# Wiring_Harness_Spec.net
KiCad netlist of a schematic drawn in Altium Designer
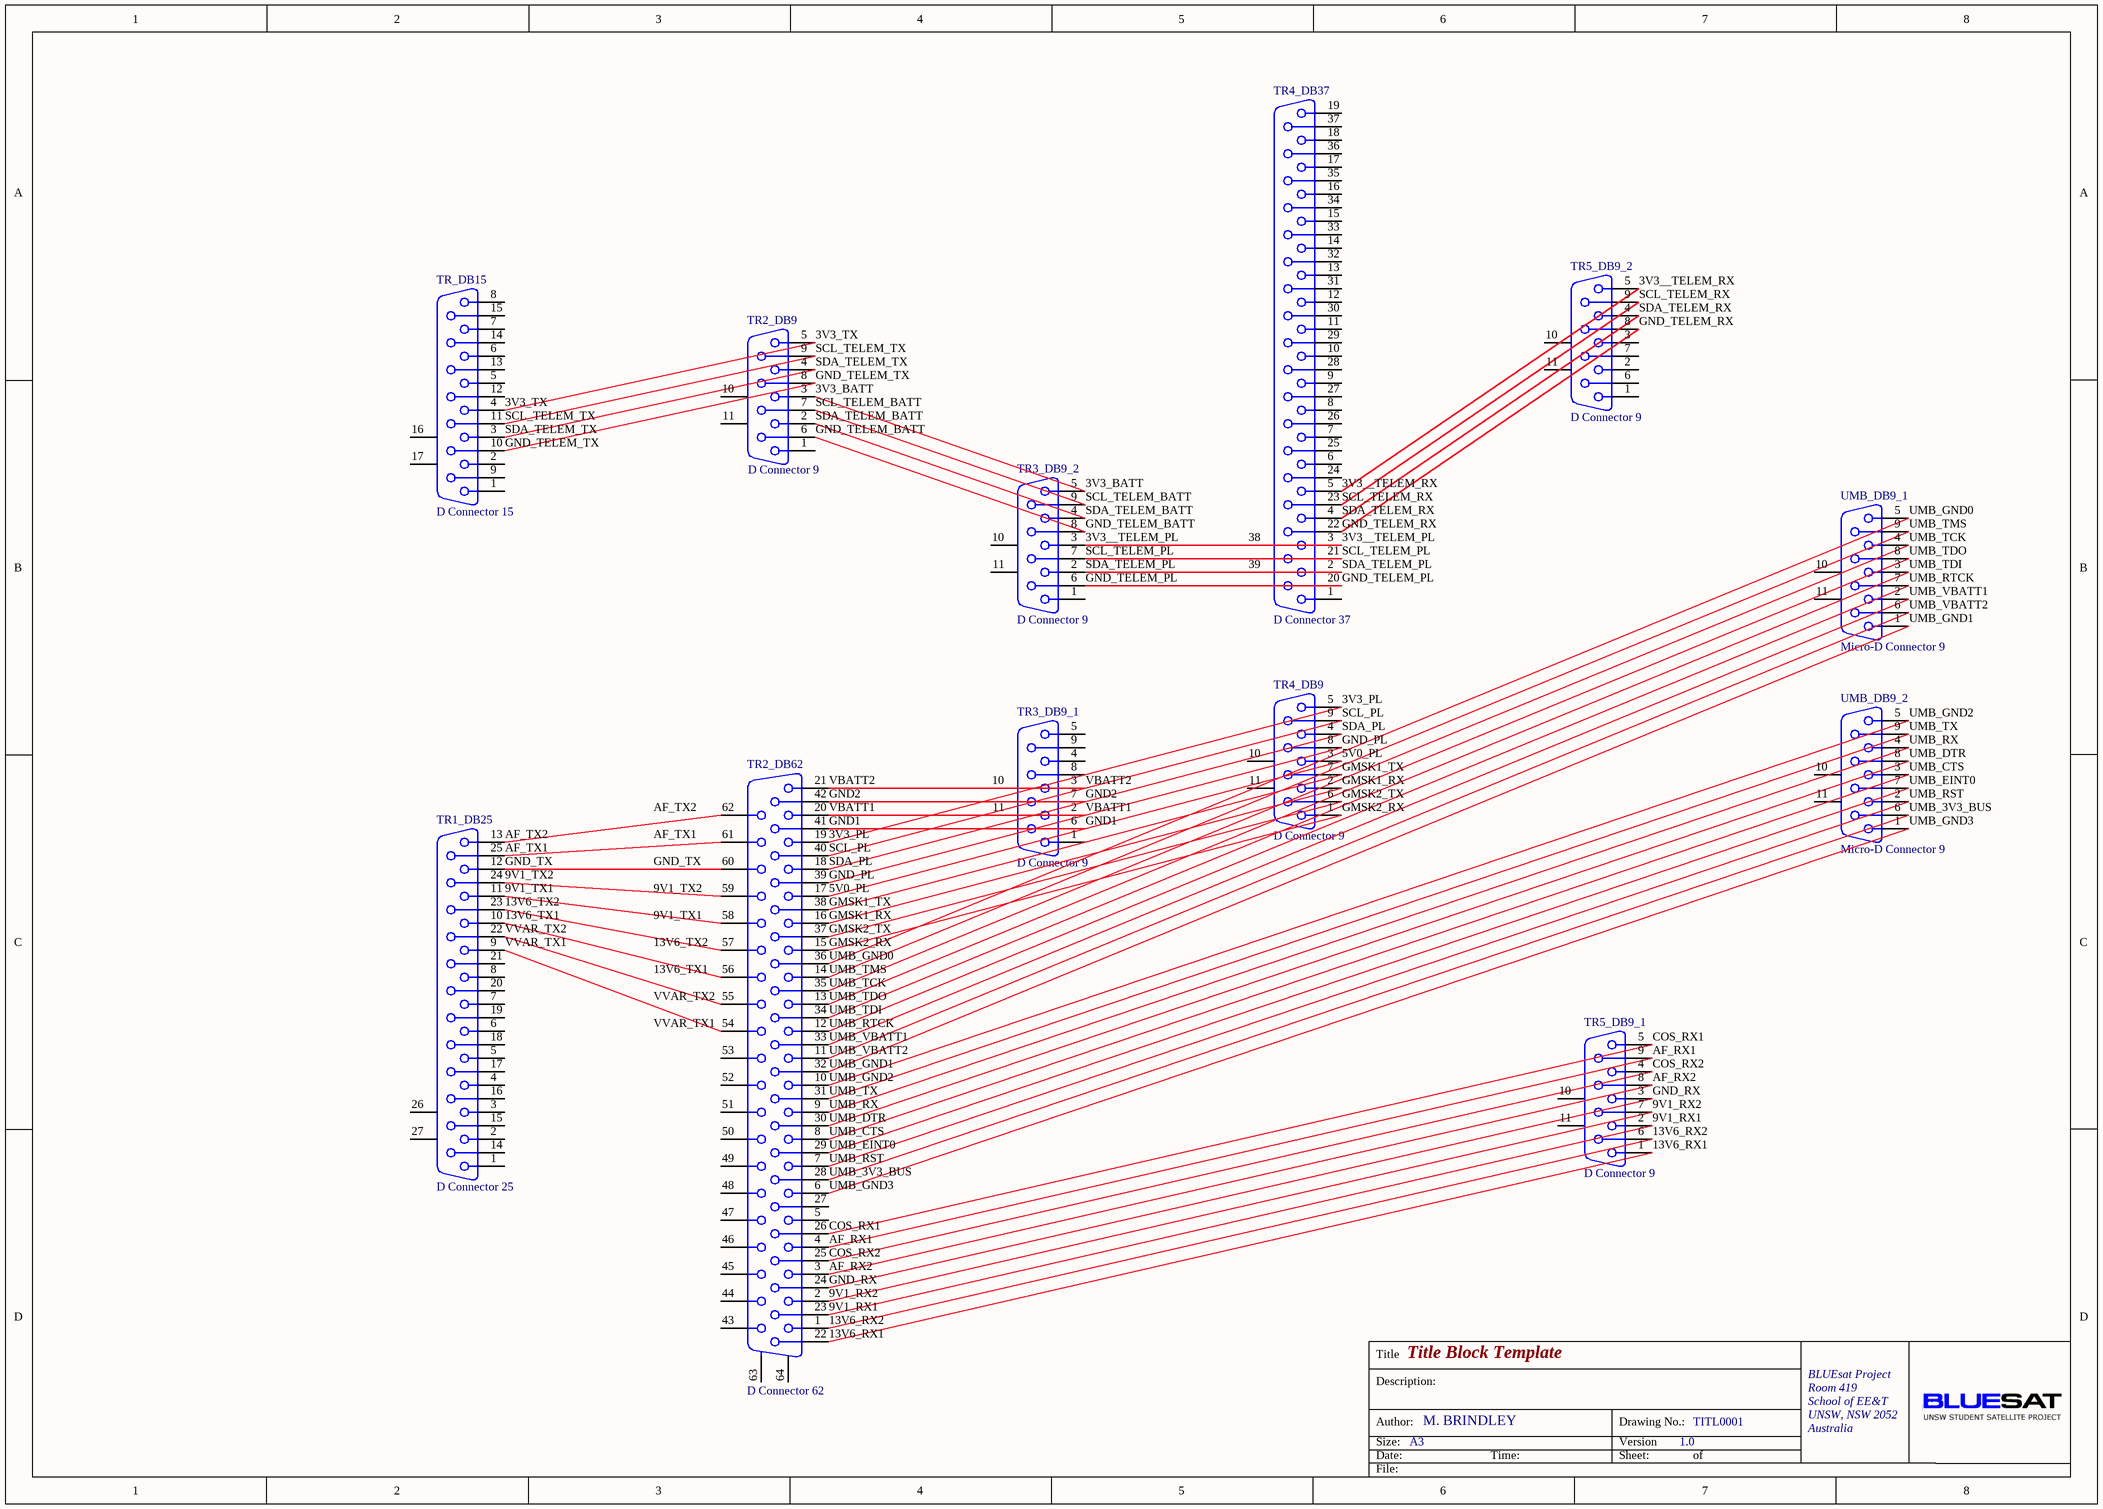
[diagram p0: Wiring Harness Spec.SchDoc]

(export (version "E")
  (design (tool "Eeschema 10.0.6"))
  (components
    (comp (ref "TR1_DB25")
      (value "D Connector 25")
      (footprint "DSUB1.385-2H25A")
      (description "Receptacle Assembly, 25 Position, Right Angle")
      (fields (field (name "PUBLISHER") "Altium Limited"))
      (libsource (lib "Miscellaneous Connectors") (part "D Connector 25"))
    )
    (comp (ref "TR2_DB9")
      (value "D Connector 9")
      (footprint "DSUB1.385-2H9")
      (description "Receptacle Assembly, 9 Position, Right Angle")
      (fields (field (name "PUBLISHER") "Altium Limited"))
      (libsource (lib "Miscellaneous Connectors") (part "D Connector 9"))
    )
    (comp (ref "TR2_DB62")
      (value "D Connector 62")
      (footprint "HD-22 62 POS")
      (libsource (lib "Tray2Mobo") (part "Connector 62"))
    )
    (comp (ref "TR3_DB9_1")
      (value "D Connector 9")
      (footprint "DSUB1.385-2H9")
      (description "Receptacle Assembly, 9 Position, Right Angle")
      (fields (field (name "PUBLISHER") "Altium Limited"))
      (libsource (lib "Miscellaneous Connectors") (part "D Connector 9"))
    )
    (comp (ref "TR3_DB9_2")
      (value "D Connector 9")
      (footprint "DSUB1.385-2H9")
      (description "Receptacle Assembly, 9 Position, Right Angle")
      (fields (field (name "PUBLISHER") "Altium Limited"))
      (libsource (lib "Miscellaneous Connectors") (part "D Connector 9"))
    )
    (comp (ref "TR4_DB9")
      (value "D Connector 9")
      (footprint "DSUB1.385-2H9")
      (description "Receptacle Assembly, 9 Position, Right Angle")
      (fields (field (name "PUBLISHER") "Altium Limited"))
      (libsource (lib "Miscellaneous Connectors") (part "D Connector 9"))
    )
    (comp (ref "TR4_DB37")
      (value "D Connector 37")
      (description "Receptacle Assembly, 37 Position, Right Angle")
      (fields (field (name "PUBLISHER") "Altium Limited"))
      (libsource (lib "Miscellaneous Connectors") (part "D Connector 37"))
    )
    (comp (ref "TR5_DB9_1")
      (value "D Connector 9")
      (footprint "DSUB1.385-2H9")
      (description "Receptacle Assembly, 9 Position, Right Angle")
      (fields (field (name "PUBLISHER") "Altium Limited"))
      (libsource (lib "Miscellaneous Connectors") (part "D Connector 9"))
    )
    (comp (ref "TR5_DB9_2")
      (value "D Connector 9")
      (footprint "DSUB1.385-2H9")
      (description "Receptacle Assembly, 9 Position, Right Angle")
      (fields (field (name "PUBLISHER") "Altium Limited"))
      (libsource (lib "Miscellaneous Connectors") (part "D Connector 9"))
    )
    (comp (ref "TR_DB15")
      (value "D Connector 15")
      (footprint "DSUB1.385-2H15")
      (description "Receptacle Assembly, 15 Position, Right Angle")
      (fields (field (name "PUBLISHER") "Altium Limited"))
      (libsource (lib "Miscellaneous Connectors") (part "D Connector 15"))
    )
    (comp (ref "UMB_DB9_1")
      (value "Micro-D Connector 9")
      (footprint "DSUB1.385-2H9")
      (description "Receptacle Assembly, 9 Position, Right Angle")
      (fields (field (name "PUBLISHER") "Altium Limited"))
      (libsource (lib "Miscellaneous Connectors") (part "D Connector 9"))
    )
    (comp (ref "UMB_DB9_2")
      (value "Micro-D Connector 9")
      (footprint "DSUB1.385-2H9")
      (description "Receptacle Assembly, 9 Position, Right Angle")
      (fields (field (name "PUBLISHER") "Altium Limited"))
      (libsource (lib "Miscellaneous Connectors") (part "D Connector 9"))
    )
  )
  (nets
    (net (code "1") (name "/3V3_BATT") (class "Default")
      (node (ref "TR2_DB9") (pin "3") (pinfunction "3_3") (pintype "passive"))
      (node (ref "TR3_DB9_2") (pin "5") (pinfunction "5_5") (pintype "passive"))
    )
    (net (code "2") (name "/3V3_PL") (class "Default")
      (node (ref "TR2_DB62") (pin "19") (pinfunction "19_19") (pintype "passive"))
      (node (ref "TR4_DB9") (pin "5") (pinfunction "5_5") (pintype "passive"))
    )
    (net (code "3") (name "/3V3_TX") (class "Default")
      (node (ref "TR2_DB9") (pin "5") (pinfunction "5_5") (pintype "passive"))
      (node (ref "TR_DB15") (pin "4") (pinfunction "4_4") (pintype "passive"))
    )
    (net (code "4") (name "/3V3__TELEM_PL") (class "Default")
      (node (ref "TR3_DB9_2") (pin "3") (pinfunction "3_3") (pintype "passive"))
      (node (ref "TR4_DB37") (pin "3") (pinfunction "3_3") (pintype "passive"))
    )
    (net (code "5") (name "/3V3__TELEM_RX") (class "Default")
      (node (ref "TR4_DB37") (pin "5") (pinfunction "5_5") (pintype "passive"))
      (node (ref "TR5_DB9_2") (pin "5") (pinfunction "5_5") (pintype "passive"))
    )
    (net (code "6") (name "/5V0_PL") (class "Default")
      (node (ref "TR2_DB62") (pin "17") (pinfunction "17_17") (pintype "passive"))
      (node (ref "TR4_DB9") (pin "3") (pinfunction "3_3") (pintype "passive"))
    )
    (net (code "7") (name "/9V1_RX1") (class "Default")
      (node (ref "TR2_DB62") (pin "23") (pinfunction "23_23") (pintype "passive"))
      (node (ref "TR5_DB9_1") (pin "2") (pinfunction "2_2") (pintype "passive"))
    )
    (net (code "8") (name "/9V1_RX2") (class "Default")
      (node (ref "TR2_DB62") (pin "2") (pinfunction "2_2") (pintype "passive"))
      (node (ref "TR5_DB9_1") (pin "7") (pinfunction "7_7") (pintype "passive"))
    )
    (net (code "9") (name "/9V1_TX1") (class "Default")
      (node (ref "TR1_DB25") (pin "11") (pinfunction "11_11") (pintype "passive"))
    )
    (net (code "10") (name "/9V1_TX2") (class "Default")
      (node (ref "TR1_DB25") (pin "24") (pinfunction "24_24") (pintype "passive"))
    )
    (net (code "11") (name "/13V6_RX1") (class "Default")
      (node (ref "TR2_DB62") (pin "22") (pinfunction "22_22") (pintype "passive"))
      (node (ref "TR5_DB9_1") (pin "1") (pinfunction "1_1") (pintype "passive"))
    )
    (net (code "12") (name "/13V6_RX2") (class "Default")
      (node (ref "TR2_DB62") (pin "1") (pinfunction "1_1") (pintype "passive"))
      (node (ref "TR5_DB9_1") (pin "6") (pinfunction "6_6") (pintype "passive"))
    )
    (net (code "13") (name "/13V6_TX1") (class "Default")
      (node (ref "TR1_DB25") (pin "10") (pinfunction "10_10") (pintype "passive"))
    )
    (net (code "14") (name "/13V6_TX2") (class "Default")
      (node (ref "TR1_DB25") (pin "23") (pinfunction "23_23") (pintype "passive"))
    )
    (net (code "15") (name "/AF_RX1") (class "Default")
      (node (ref "TR2_DB62") (pin "4") (pinfunction "4_4") (pintype "passive"))
      (node (ref "TR5_DB9_1") (pin "9") (pinfunction "9_9") (pintype "passive"))
    )
    (net (code "16") (name "/AF_RX2") (class "Default")
      (node (ref "TR2_DB62") (pin "3") (pinfunction "3_3") (pintype "passive"))
      (node (ref "TR5_DB9_1") (pin "8") (pinfunction "8_8") (pintype "passive"))
    )
    (net (code "17") (name "/AF_TX1") (class "Default")
      (node (ref "TR1_DB25") (pin "25") (pinfunction "25_25") (pintype "passive"))
    )
    (net (code "18") (name "/AF_TX2") (class "Default")
      (node (ref "TR1_DB25") (pin "13") (pinfunction "13_13") (pintype "passive"))
    )
    (net (code "19") (name "/COS_RX1") (class "Default")
      (node (ref "TR2_DB62") (pin "26") (pinfunction "26_26") (pintype "passive"))
      (node (ref "TR5_DB9_1") (pin "5") (pinfunction "5_5") (pintype "passive"))
    )
    (net (code "20") (name "/COS_RX2") (class "Default")
      (node (ref "TR2_DB62") (pin "25") (pinfunction "25_25") (pintype "passive"))
      (node (ref "TR5_DB9_1") (pin "4") (pinfunction "4_4") (pintype "passive"))
    )
    (net (code "21") (name "/GMSK1_RX") (class "Default")
      (node (ref "TR2_DB62") (pin "16") (pinfunction "16_16") (pintype "passive"))
      (node (ref "TR4_DB9") (pin "2") (pinfunction "2_2") (pintype "passive"))
    )
    (net (code "22") (name "/GMSK1_TX") (class "Default")
      (node (ref "TR2_DB62") (pin "38") (pinfunction "38_38") (pintype "passive"))
      (node (ref "TR4_DB9") (pin "7") (pinfunction "7_7") (pintype "passive"))
    )
    (net (code "23") (name "/GMSK2_RX") (class "Default")
      (node (ref "TR2_DB62") (pin "15") (pinfunction "15_15") (pintype "passive"))
      (node (ref "TR4_DB9") (pin "1") (pinfunction "1_1") (pintype "passive"))
    )
    (net (code "24") (name "/GMSK2_TX") (class "Default")
      (node (ref "TR2_DB62") (pin "37") (pinfunction "37_37") (pintype "passive"))
      (node (ref "TR4_DB9") (pin "6") (pinfunction "6_6") (pintype "passive"))
    )
    (net (code "25") (name "/GND1") (class "Default")
      (node (ref "TR2_DB62") (pin "41") (pinfunction "41_41") (pintype "passive"))
      (node (ref "TR3_DB9_1") (pin "6") (pinfunction "6_6") (pintype "passive"))
    )
    (net (code "26") (name "/GND2") (class "Default")
      (node (ref "TR2_DB62") (pin "42") (pinfunction "42_42") (pintype "passive"))
      (node (ref "TR3_DB9_1") (pin "7") (pinfunction "7_7") (pintype "passive"))
    )
    (net (code "27") (name "/GND_PL") (class "Default")
      (node (ref "TR2_DB62") (pin "39") (pinfunction "39_39") (pintype "passive"))
      (node (ref "TR4_DB9") (pin "8") (pinfunction "8_8") (pintype "passive"))
    )
    (net (code "28") (name "/GND_RX") (class "Default")
      (node (ref "TR2_DB62") (pin "24") (pinfunction "24_24") (pintype "passive"))
      (node (ref "TR5_DB9_1") (pin "3") (pinfunction "3_3") (pintype "passive"))
    )
    (net (code "29") (name "/GND_TELEM_BATT") (class "Default")
      (node (ref "TR2_DB9") (pin "6") (pinfunction "6_6") (pintype "passive"))
      (node (ref "TR3_DB9_2") (pin "8") (pinfunction "8_8") (pintype "passive"))
    )
    (net (code "30") (name "/GND_TELEM_PL") (class "Default")
      (node (ref "TR3_DB9_2") (pin "6") (pinfunction "6_6") (pintype "passive"))
      (node (ref "TR4_DB37") (pin "20") (pinfunction "20_20") (pintype "passive"))
    )
    (net (code "31") (name "/GND_TELEM_RX") (class "Default")
      (node (ref "TR4_DB37") (pin "22") (pinfunction "22_22") (pintype "passive"))
      (node (ref "TR5_DB9_2") (pin "8") (pinfunction "8_8") (pintype "passive"))
    )
    (net (code "32") (name "/GND_TELEM_TX") (class "Default")
      (node (ref "TR2_DB9") (pin "8") (pinfunction "8_8") (pintype "passive"))
      (node (ref "TR_DB15") (pin "10") (pinfunction "10_10") (pintype "passive"))
    )
    (net (code "33") (name "/GND_TX") (class "Default")
      (node (ref "TR1_DB25") (pin "12") (pinfunction "12_12") (pintype "passive"))
    )
    (net (code "34") (name "/SCL_PL") (class "Default")
      (node (ref "TR2_DB62") (pin "40") (pinfunction "40_40") (pintype "passive"))
      (node (ref "TR4_DB9") (pin "9") (pinfunction "9_9") (pintype "passive"))
    )
    (net (code "35") (name "/SCL_TELEM_BATT") (class "Default")
      (node (ref "TR2_DB9") (pin "7") (pinfunction "7_7") (pintype "passive"))
      (node (ref "TR3_DB9_2") (pin "9") (pinfunction "9_9") (pintype "passive"))
    )
    (net (code "36") (name "/SCL_TELEM_PL") (class "Default")
      (node (ref "TR3_DB9_2") (pin "7") (pinfunction "7_7") (pintype "passive"))
      (node (ref "TR4_DB37") (pin "21") (pinfunction "21_21") (pintype "passive"))
    )
    (net (code "37") (name "/SCL_TELEM_RX") (class "Default")
      (node (ref "TR4_DB37") (pin "23") (pinfunction "23_23") (pintype "passive"))
      (node (ref "TR5_DB9_2") (pin "9") (pinfunction "9_9") (pintype "passive"))
    )
    (net (code "38") (name "/SCL_TELEM_TX") (class "Default")
      (node (ref "TR2_DB9") (pin "9") (pinfunction "9_9") (pintype "passive"))
      (node (ref "TR_DB15") (pin "11") (pinfunction "11_11") (pintype "passive"))
    )
    (net (code "39") (name "/SDA_PL") (class "Default")
      (node (ref "TR2_DB62") (pin "18") (pinfunction "18_18") (pintype "passive"))
      (node (ref "TR4_DB9") (pin "4") (pinfunction "4_4") (pintype "passive"))
    )
    (net (code "40") (name "/SDA_TELEM_BATT") (class "Default")
      (node (ref "TR2_DB9") (pin "2") (pinfunction "2_2") (pintype "passive"))
      (node (ref "TR3_DB9_2") (pin "4") (pinfunction "4_4") (pintype "passive"))
    )
    (net (code "41") (name "/SDA_TELEM_PL") (class "Default")
      (node (ref "TR3_DB9_2") (pin "2") (pinfunction "2_2") (pintype "passive"))
      (node (ref "TR4_DB37") (pin "2") (pinfunction "2_2") (pintype "passive"))
    )
    (net (code "42") (name "/SDA_TELEM_RX") (class "Default")
      (node (ref "TR4_DB37") (pin "4") (pinfunction "4_4") (pintype "passive"))
      (node (ref "TR5_DB9_2") (pin "4") (pinfunction "4_4") (pintype "passive"))
    )
    (net (code "43") (name "/SDA_TELEM_TX") (class "Default")
      (node (ref "TR2_DB9") (pin "4") (pinfunction "4_4") (pintype "passive"))
      (node (ref "TR_DB15") (pin "3") (pinfunction "3_3") (pintype "passive"))
    )
    (net (code "44") (name "/UMB_3V3_BUS") (class "Default")
      (node (ref "TR2_DB62") (pin "28") (pinfunction "28_28") (pintype "passive"))
      (node (ref "UMB_DB9_2") (pin "6") (pinfunction "6_6") (pintype "passive"))
    )
    (net (code "45") (name "/UMB_CTS") (class "Default")
      (node (ref "TR2_DB62") (pin "8") (pinfunction "8_8") (pintype "passive"))
      (node (ref "UMB_DB9_2") (pin "3") (pinfunction "3_3") (pintype "passive"))
    )
    (net (code "46") (name "/UMB_DTR") (class "Default")
      (node (ref "TR2_DB62") (pin "30") (pinfunction "30_30") (pintype "passive"))
      (node (ref "UMB_DB9_2") (pin "8") (pinfunction "8_8") (pintype "passive"))
    )
    (net (code "47") (name "/UMB_EINT0") (class "Default")
      (node (ref "TR2_DB62") (pin "29") (pinfunction "29_29") (pintype "passive"))
      (node (ref "UMB_DB9_2") (pin "7") (pinfunction "7_7") (pintype "passive"))
    )
    (net (code "48") (name "/UMB_GND0") (class "Default")
      (node (ref "TR2_DB62") (pin "36") (pinfunction "36_36") (pintype "passive"))
      (node (ref "UMB_DB9_1") (pin "5") (pinfunction "5_5") (pintype "passive"))
    )
    (net (code "49") (name "/UMB_GND1") (class "Default")
      (node (ref "TR2_DB62") (pin "32") (pinfunction "32_32") (pintype "passive"))
      (node (ref "UMB_DB9_1") (pin "1") (pinfunction "1_1") (pintype "passive"))
    )
    (net (code "50") (name "/UMB_GND2") (class "Default")
      (node (ref "TR2_DB62") (pin "10") (pinfunction "10_10") (pintype "passive"))
      (node (ref "UMB_DB9_2") (pin "5") (pinfunction "5_5") (pintype "passive"))
    )
    (net (code "51") (name "/UMB_GND3") (class "Default")
      (node (ref "TR2_DB62") (pin "6") (pinfunction "6_6") (pintype "passive"))
      (node (ref "UMB_DB9_2") (pin "1") (pinfunction "1_1") (pintype "passive"))
    )
    (net (code "52") (name "/UMB_RST") (class "Default")
      (node (ref "TR2_DB62") (pin "7") (pinfunction "7_7") (pintype "passive"))
      (node (ref "UMB_DB9_2") (pin "2") (pinfunction "2_2") (pintype "passive"))
    )
    (net (code "53") (name "/UMB_RTCK") (class "Default")
      (node (ref "TR2_DB62") (pin "12") (pinfunction "12_12") (pintype "passive"))
      (node (ref "UMB_DB9_1") (pin "7") (pinfunction "7_7") (pintype "passive"))
    )
    (net (code "54") (name "/UMB_RX") (class "Default")
      (node (ref "TR2_DB62") (pin "9") (pinfunction "9_9") (pintype "passive"))
      (node (ref "UMB_DB9_2") (pin "4") (pinfunction "4_4") (pintype "passive"))
    )
    (net (code "55") (name "/UMB_TCK") (class "Default")
      (node (ref "TR2_DB62") (pin "35") (pinfunction "35_35") (pintype "passive"))
      (node (ref "UMB_DB9_1") (pin "4") (pinfunction "4_4") (pintype "passive"))
    )
    (net (code "56") (name "/UMB_TDI") (class "Default")
      (node (ref "TR2_DB62") (pin "34") (pinfunction "34_34") (pintype "passive"))
      (node (ref "UMB_DB9_1") (pin "3") (pinfunction "3_3") (pintype "passive"))
    )
    (net (code "57") (name "/UMB_TDO") (class "Default")
      (node (ref "TR2_DB62") (pin "13") (pinfunction "13_13") (pintype "passive"))
      (node (ref "UMB_DB9_1") (pin "8") (pinfunction "8_8") (pintype "passive"))
    )
    (net (code "58") (name "/UMB_TMS") (class "Default")
      (node (ref "TR2_DB62") (pin "14") (pinfunction "14_14") (pintype "passive"))
      (node (ref "UMB_DB9_1") (pin "9") (pinfunction "9_9") (pintype "passive"))
    )
    (net (code "59") (name "/UMB_TX") (class "Default")
      (node (ref "TR2_DB62") (pin "31") (pinfunction "31_31") (pintype "passive"))
      (node (ref "UMB_DB9_2") (pin "9") (pinfunction "9_9") (pintype "passive"))
    )
    (net (code "60") (name "/UMB_VBATT1") (class "Default")
      (node (ref "TR2_DB62") (pin "33") (pinfunction "33_33") (pintype "passive"))
      (node (ref "UMB_DB9_1") (pin "2") (pinfunction "2_2") (pintype "passive"))
    )
    (net (code "61") (name "/UMB_VBATT2") (class "Default")
      (node (ref "TR2_DB62") (pin "11") (pinfunction "11_11") (pintype "passive"))
      (node (ref "UMB_DB9_1") (pin "6") (pinfunction "6_6") (pintype "passive"))
    )
    (net (code "62") (name "/VBATT1") (class "Default")
      (node (ref "TR2_DB62") (pin "20") (pinfunction "20_20") (pintype "passive"))
      (node (ref "TR3_DB9_1") (pin "2") (pinfunction "2_2") (pintype "passive"))
    )
    (net (code "63") (name "/VBATT2") (class "Default")
      (node (ref "TR2_DB62") (pin "21") (pinfunction "21_21") (pintype "passive"))
      (node (ref "TR3_DB9_1") (pin "3") (pinfunction "3_3") (pintype "passive"))
    )
    (net (code "64") (name "/VVAR_TX1") (class "Default")
      (node (ref "TR1_DB25") (pin "9") (pinfunction "9_9") (pintype "passive"))
    )
    (net (code "65") (name "/VVAR_TX2") (class "Default")
      (node (ref "TR1_DB25") (pin "22") (pinfunction "22_22") (pintype "passive"))
    )
    (net (code "66") (name "unconnected-(TR1_DB25-MH1-Pad26)") (class "Default")
      (node (ref "TR1_DB25") (pin "26") (pinfunction "MH1_26") (pintype "passive"))
    )
    (net (code "67") (name "unconnected-(TR1_DB25-MH2-Pad27)") (class "Default")
      (node (ref "TR1_DB25") (pin "27") (pinfunction "MH2_27") (pintype "passive"))
    )
    (net (code "68") (name "unconnected-(TR1_DB25-Pad1)") (class "Default")
      (node (ref "TR1_DB25") (pin "1") (pinfunction "1_1") (pintype "passive"))
    )
    (net (code "69") (name "unconnected-(TR1_DB25-Pad2)") (class "Default")
      (node (ref "TR1_DB25") (pin "2") (pinfunction "2_2") (pintype "passive"))
    )
    (net (code "70") (name "unconnected-(TR1_DB25-Pad3)") (class "Default")
      (node (ref "TR1_DB25") (pin "3") (pinfunction "3_3") (pintype "passive"))
    )
    (net (code "71") (name "unconnected-(TR1_DB25-Pad4)") (class "Default")
      (node (ref "TR1_DB25") (pin "4") (pinfunction "4_4") (pintype "passive"))
    )
    (net (code "72") (name "unconnected-(TR1_DB25-Pad5)") (class "Default")
      (node (ref "TR1_DB25") (pin "5") (pinfunction "5_5") (pintype "passive"))
    )
    (net (code "73") (name "unconnected-(TR1_DB25-Pad6)") (class "Default")
      (node (ref "TR1_DB25") (pin "6") (pinfunction "6_6") (pintype "passive"))
    )
    (net (code "74") (name "unconnected-(TR1_DB25-Pad7)") (class "Default")
      (node (ref "TR1_DB25") (pin "7") (pinfunction "7_7") (pintype "passive"))
    )
    (net (code "75") (name "unconnected-(TR1_DB25-Pad8)") (class "Default")
      (node (ref "TR1_DB25") (pin "8") (pinfunction "8_8") (pintype "passive"))
    )
    (net (code "76") (name "unconnected-(TR1_DB25-Pad14)") (class "Default")
      (node (ref "TR1_DB25") (pin "14") (pinfunction "14_14") (pintype "passive"))
    )
    (net (code "77") (name "unconnected-(TR1_DB25-Pad15)") (class "Default")
      (node (ref "TR1_DB25") (pin "15") (pinfunction "15_15") (pintype "passive"))
    )
    (net (code "78") (name "unconnected-(TR1_DB25-Pad16)") (class "Default")
      (node (ref "TR1_DB25") (pin "16") (pinfunction "16_16") (pintype "passive"))
    )
    (net (code "79") (name "unconnected-(TR1_DB25-Pad17)") (class "Default")
      (node (ref "TR1_DB25") (pin "17") (pinfunction "17_17") (pintype "passive"))
    )
    (net (code "80") (name "unconnected-(TR1_DB25-Pad18)") (class "Default")
      (node (ref "TR1_DB25") (pin "18") (pinfunction "18_18") (pintype "passive"))
    )
    (net (code "81") (name "unconnected-(TR1_DB25-Pad19)") (class "Default")
      (node (ref "TR1_DB25") (pin "19") (pinfunction "19_19") (pintype "passive"))
    )
    (net (code "82") (name "unconnected-(TR1_DB25-Pad20)") (class "Default")
      (node (ref "TR1_DB25") (pin "20") (pinfunction "20_20") (pintype "passive"))
    )
    (net (code "83") (name "unconnected-(TR1_DB25-Pad21)") (class "Default")
      (node (ref "TR1_DB25") (pin "21") (pinfunction "21_21") (pintype "passive"))
    )
    (net (code "84") (name "unconnected-(TR2_DB9-MH1-Pad10)") (class "Default")
      (node (ref "TR2_DB9") (pin "10") (pinfunction "MH1_10") (pintype "passive"))
    )
    (net (code "85") (name "unconnected-(TR2_DB9-MH2-Pad11)") (class "Default")
      (node (ref "TR2_DB9") (pin "11") (pinfunction "MH2_11") (pintype "passive"))
    )
    (net (code "86") (name "unconnected-(TR2_DB9-Pad1)") (class "Default")
      (node (ref "TR2_DB9") (pin "1") (pinfunction "1_1") (pintype "passive"))
    )
    (net (code "87") (name "unconnected-(TR2_DB62-MH1-Pad63)") (class "Default")
      (node (ref "TR2_DB62") (pin "63") (pinfunction "MH1_63") (pintype "passive"))
    )
    (net (code "88") (name "unconnected-(TR2_DB62-MH2-Pad64)") (class "Default")
      (node (ref "TR2_DB62") (pin "64") (pinfunction "MH2_64") (pintype "passive"))
    )
    (net (code "89") (name "unconnected-(TR2_DB62-Pad5)") (class "Default")
      (node (ref "TR2_DB62") (pin "5") (pinfunction "5_5") (pintype "passive"))
    )
    (net (code "90") (name "unconnected-(TR2_DB62-Pad27)") (class "Default")
      (node (ref "TR2_DB62") (pin "27") (pinfunction "27_27") (pintype "passive"))
    )
    (net (code "91") (name "unconnected-(TR2_DB62-Pad43)") (class "Default")
      (node (ref "TR2_DB62") (pin "43") (pinfunction "43_43") (pintype "passive"))
    )
    (net (code "92") (name "unconnected-(TR2_DB62-Pad44)") (class "Default")
      (node (ref "TR2_DB62") (pin "44") (pinfunction "44_44") (pintype "passive"))
    )
    (net (code "93") (name "unconnected-(TR2_DB62-Pad45)") (class "Default")
      (node (ref "TR2_DB62") (pin "45") (pinfunction "45_45") (pintype "passive"))
    )
    (net (code "94") (name "unconnected-(TR2_DB62-Pad46)") (class "Default")
      (node (ref "TR2_DB62") (pin "46") (pinfunction "46_46") (pintype "passive"))
    )
    (net (code "95") (name "unconnected-(TR2_DB62-Pad47)") (class "Default")
      (node (ref "TR2_DB62") (pin "47") (pinfunction "47_47") (pintype "passive"))
    )
    (net (code "96") (name "unconnected-(TR2_DB62-Pad48)") (class "Default")
      (node (ref "TR2_DB62") (pin "48") (pinfunction "48_48") (pintype "passive"))
    )
    (net (code "97") (name "unconnected-(TR2_DB62-Pad49)") (class "Default")
      (node (ref "TR2_DB62") (pin "49") (pinfunction "49_49") (pintype "passive"))
    )
    (net (code "98") (name "unconnected-(TR2_DB62-Pad50)") (class "Default")
      (node (ref "TR2_DB62") (pin "50") (pinfunction "50_50") (pintype "passive"))
    )
    (net (code "99") (name "unconnected-(TR2_DB62-Pad51)") (class "Default")
      (node (ref "TR2_DB62") (pin "51") (pinfunction "51_51") (pintype "passive"))
    )
    (net (code "100") (name "unconnected-(TR2_DB62-Pad52)") (class "Default")
      (node (ref "TR2_DB62") (pin "52") (pinfunction "52_52") (pintype "passive"))
    )
    (net (code "101") (name "unconnected-(TR2_DB62-Pad53)") (class "Default")
      (node (ref "TR2_DB62") (pin "53") (pinfunction "53_53") (pintype "passive"))
    )
    (net (code "102") (name "unconnected-(TR2_DB62-Pad54)") (class "Default")
      (node (ref "TR2_DB62") (pin "54") (pinfunction "54_54") (pintype "passive"))
    )
    (net (code "103") (name "unconnected-(TR2_DB62-Pad55)") (class "Default")
      (node (ref "TR2_DB62") (pin "55") (pinfunction "55_55") (pintype "passive"))
    )
    (net (code "104") (name "unconnected-(TR2_DB62-Pad56)") (class "Default")
      (node (ref "TR2_DB62") (pin "56") (pinfunction "56_56") (pintype "passive"))
    )
    (net (code "105") (name "unconnected-(TR2_DB62-Pad57)") (class "Default")
      (node (ref "TR2_DB62") (pin "57") (pinfunction "57_57") (pintype "passive"))
    )
    (net (code "106") (name "unconnected-(TR2_DB62-Pad58)") (class "Default")
      (node (ref "TR2_DB62") (pin "58") (pinfunction "58_58") (pintype "passive"))
    )
    (net (code "107") (name "unconnected-(TR2_DB62-Pad59)") (class "Default")
      (node (ref "TR2_DB62") (pin "59") (pinfunction "59_59") (pintype "passive"))
    )
    (net (code "108") (name "unconnected-(TR2_DB62-Pad60)") (class "Default")
      (node (ref "TR2_DB62") (pin "60") (pinfunction "60_60") (pintype "passive"))
    )
    (net (code "109") (name "unconnected-(TR2_DB62-Pad61)") (class "Default")
      (node (ref "TR2_DB62") (pin "61") (pinfunction "61_61") (pintype "passive"))
    )
    (net (code "110") (name "unconnected-(TR2_DB62-Pad62)") (class "Default")
      (node (ref "TR2_DB62") (pin "62") (pinfunction "62_62") (pintype "passive"))
    )
    (net (code "111") (name "unconnected-(TR3_DB9_1-MH1-Pad10)") (class "Default")
      (node (ref "TR3_DB9_1") (pin "10") (pinfunction "MH1_10") (pintype "passive"))
    )
    (net (code "112") (name "unconnected-(TR3_DB9_1-MH2-Pad11)") (class "Default")
      (node (ref "TR3_DB9_1") (pin "11") (pinfunction "MH2_11") (pintype "passive"))
    )
    (net (code "113") (name "unconnected-(TR3_DB9_1-Pad1)") (class "Default")
      (node (ref "TR3_DB9_1") (pin "1") (pinfunction "1_1") (pintype "passive"))
    )
    (net (code "114") (name "unconnected-(TR3_DB9_1-Pad4)") (class "Default")
      (node (ref "TR3_DB9_1") (pin "4") (pinfunction "4_4") (pintype "passive"))
    )
    (net (code "115") (name "unconnected-(TR3_DB9_1-Pad5)") (class "Default")
      (node (ref "TR3_DB9_1") (pin "5") (pinfunction "5_5") (pintype "passive"))
    )
    (net (code "116") (name "unconnected-(TR3_DB9_1-Pad8)") (class "Default")
      (node (ref "TR3_DB9_1") (pin "8") (pinfunction "8_8") (pintype "passive"))
    )
    (net (code "117") (name "unconnected-(TR3_DB9_1-Pad9)") (class "Default")
      (node (ref "TR3_DB9_1") (pin "9") (pinfunction "9_9") (pintype "passive"))
    )
    (net (code "118") (name "unconnected-(TR3_DB9_2-MH1-Pad10)") (class "Default")
      (node (ref "TR3_DB9_2") (pin "10") (pinfunction "MH1_10") (pintype "passive"))
    )
    (net (code "119") (name "unconnected-(TR3_DB9_2-MH2-Pad11)") (class "Default")
      (node (ref "TR3_DB9_2") (pin "11") (pinfunction "MH2_11") (pintype "passive"))
    )
    (net (code "120") (name "unconnected-(TR3_DB9_2-Pad1)") (class "Default")
      (node (ref "TR3_DB9_2") (pin "1") (pinfunction "1_1") (pintype "passive"))
    )
    (net (code "121") (name "unconnected-(TR4_DB9-MH1-Pad10)") (class "Default")
      (node (ref "TR4_DB9") (pin "10") (pinfunction "MH1_10") (pintype "passive"))
    )
    (net (code "122") (name "unconnected-(TR4_DB9-MH2-Pad11)") (class "Default")
      (node (ref "TR4_DB9") (pin "11") (pinfunction "MH2_11") (pintype "passive"))
    )
    (net (code "123") (name "unconnected-(TR4_DB37-MH1-Pad38)") (class "Default")
      (node (ref "TR4_DB37") (pin "38") (pinfunction "MH1_38") (pintype "passive"))
    )
    (net (code "124") (name "unconnected-(TR4_DB37-MH2-Pad39)") (class "Default")
      (node (ref "TR4_DB37") (pin "39") (pinfunction "MH2_39") (pintype "passive"))
    )
    (net (code "125") (name "unconnected-(TR4_DB37-Pad1)") (class "Default")
      (node (ref "TR4_DB37") (pin "1") (pinfunction "1_1") (pintype "passive"))
    )
    (net (code "126") (name "unconnected-(TR4_DB37-Pad6)") (class "Default")
      (node (ref "TR4_DB37") (pin "6") (pinfunction "6_6") (pintype "passive"))
    )
    (net (code "127") (name "unconnected-(TR4_DB37-Pad7)") (class "Default")
      (node (ref "TR4_DB37") (pin "7") (pinfunction "7_7") (pintype "passive"))
    )
    (net (code "128") (name "unconnected-(TR4_DB37-Pad8)") (class "Default")
      (node (ref "TR4_DB37") (pin "8") (pinfunction "8_8") (pintype "passive"))
    )
    (net (code "129") (name "unconnected-(TR4_DB37-Pad9)") (class "Default")
      (node (ref "TR4_DB37") (pin "9") (pinfunction "9_9") (pintype "passive"))
    )
    (net (code "130") (name "unconnected-(TR4_DB37-Pad10)") (class "Default")
      (node (ref "TR4_DB37") (pin "10") (pinfunction "10_10") (pintype "passive"))
    )
    (net (code "131") (name "unconnected-(TR4_DB37-Pad11)") (class "Default")
      (node (ref "TR4_DB37") (pin "11") (pinfunction "11_11") (pintype "passive"))
    )
    (net (code "132") (name "unconnected-(TR4_DB37-Pad12)") (class "Default")
      (node (ref "TR4_DB37") (pin "12") (pinfunction "12_12") (pintype "passive"))
    )
    (net (code "133") (name "unconnected-(TR4_DB37-Pad13)") (class "Default")
      (node (ref "TR4_DB37") (pin "13") (pinfunction "13_13") (pintype "passive"))
    )
    (net (code "134") (name "unconnected-(TR4_DB37-Pad14)") (class "Default")
      (node (ref "TR4_DB37") (pin "14") (pinfunction "14_14") (pintype "passive"))
    )
    (net (code "135") (name "unconnected-(TR4_DB37-Pad15)") (class "Default")
      (node (ref "TR4_DB37") (pin "15") (pinfunction "15_15") (pintype "passive"))
    )
    (net (code "136") (name "unconnected-(TR4_DB37-Pad16)") (class "Default")
      (node (ref "TR4_DB37") (pin "16") (pinfunction "16_16") (pintype "passive"))
    )
    (net (code "137") (name "unconnected-(TR4_DB37-Pad17)") (class "Default")
      (node (ref "TR4_DB37") (pin "17") (pinfunction "17_17") (pintype "passive"))
    )
    (net (code "138") (name "unconnected-(TR4_DB37-Pad18)") (class "Default")
      (node (ref "TR4_DB37") (pin "18") (pinfunction "18_18") (pintype "passive"))
    )
    (net (code "139") (name "unconnected-(TR4_DB37-Pad19)") (class "Default")
      (node (ref "TR4_DB37") (pin "19") (pinfunction "19_19") (pintype "passive"))
    )
    (net (code "140") (name "unconnected-(TR4_DB37-Pad24)") (class "Default")
      (node (ref "TR4_DB37") (pin "24") (pinfunction "24_24") (pintype "passive"))
    )
    (net (code "141") (name "unconnected-(TR4_DB37-Pad25)") (class "Default")
      (node (ref "TR4_DB37") (pin "25") (pinfunction "25_25") (pintype "passive"))
    )
    (net (code "142") (name "unconnected-(TR4_DB37-Pad26)") (class "Default")
      (node (ref "TR4_DB37") (pin "26") (pinfunction "26_26") (pintype "passive"))
    )
    (net (code "143") (name "unconnected-(TR4_DB37-Pad27)") (class "Default")
      (node (ref "TR4_DB37") (pin "27") (pinfunction "27_27") (pintype "passive"))
    )
    (net (code "144") (name "unconnected-(TR4_DB37-Pad28)") (class "Default")
      (node (ref "TR4_DB37") (pin "28") (pinfunction "28_28") (pintype "passive"))
    )
    (net (code "145") (name "unconnected-(TR4_DB37-Pad29)") (class "Default")
      (node (ref "TR4_DB37") (pin "29") (pinfunction "29_29") (pintype "passive"))
    )
    (net (code "146") (name "unconnected-(TR4_DB37-Pad30)") (class "Default")
      (node (ref "TR4_DB37") (pin "30") (pinfunction "30_30") (pintype "passive"))
    )
    (net (code "147") (name "unconnected-(TR4_DB37-Pad31)") (class "Default")
      (node (ref "TR4_DB37") (pin "31") (pinfunction "31_31") (pintype "passive"))
    )
    (net (code "148") (name "unconnected-(TR4_DB37-Pad32)") (class "Default")
      (node (ref "TR4_DB37") (pin "32") (pinfunction "32_32") (pintype "passive"))
    )
    (net (code "149") (name "unconnected-(TR4_DB37-Pad33)") (class "Default")
      (node (ref "TR4_DB37") (pin "33") (pinfunction "33_33") (pintype "passive"))
    )
    (net (code "150") (name "unconnected-(TR4_DB37-Pad34)") (class "Default")
      (node (ref "TR4_DB37") (pin "34") (pinfunction "34_34") (pintype "passive"))
    )
    (net (code "151") (name "unconnected-(TR4_DB37-Pad35)") (class "Default")
      (node (ref "TR4_DB37") (pin "35") (pinfunction "35_35") (pintype "passive"))
    )
    (net (code "152") (name "unconnected-(TR4_DB37-Pad36)") (class "Default")
      (node (ref "TR4_DB37") (pin "36") (pinfunction "36_36") (pintype "passive"))
    )
    (net (code "153") (name "unconnected-(TR4_DB37-Pad37)") (class "Default")
      (node (ref "TR4_DB37") (pin "37") (pinfunction "37_37") (pintype "passive"))
    )
    (net (code "154") (name "unconnected-(TR5_DB9_1-MH1-Pad10)") (class "Default")
      (node (ref "TR5_DB9_1") (pin "10") (pinfunction "MH1_10") (pintype "passive"))
    )
    (net (code "155") (name "unconnected-(TR5_DB9_1-MH2-Pad11)") (class "Default")
      (node (ref "TR5_DB9_1") (pin "11") (pinfunction "MH2_11") (pintype "passive"))
    )
    (net (code "156") (name "unconnected-(TR5_DB9_2-MH1-Pad10)") (class "Default")
      (node (ref "TR5_DB9_2") (pin "10") (pinfunction "MH1_10") (pintype "passive"))
    )
    (net (code "157") (name "unconnected-(TR5_DB9_2-MH2-Pad11)") (class "Default")
      (node (ref "TR5_DB9_2") (pin "11") (pinfunction "MH2_11") (pintype "passive"))
    )
    (net (code "158") (name "unconnected-(TR5_DB9_2-Pad1)") (class "Default")
      (node (ref "TR5_DB9_2") (pin "1") (pinfunction "1_1") (pintype "passive"))
    )
    (net (code "159") (name "unconnected-(TR5_DB9_2-Pad2)") (class "Default")
      (node (ref "TR5_DB9_2") (pin "2") (pinfunction "2_2") (pintype "passive"))
    )
    (net (code "160") (name "unconnected-(TR5_DB9_2-Pad3)") (class "Default")
      (node (ref "TR5_DB9_2") (pin "3") (pinfunction "3_3") (pintype "passive"))
    )
    (net (code "161") (name "unconnected-(TR5_DB9_2-Pad6)") (class "Default")
      (node (ref "TR5_DB9_2") (pin "6") (pinfunction "6_6") (pintype "passive"))
    )
    (net (code "162") (name "unconnected-(TR5_DB9_2-Pad7)") (class "Default")
      (node (ref "TR5_DB9_2") (pin "7") (pinfunction "7_7") (pintype "passive"))
    )
    (net (code "163") (name "unconnected-(TR_DB15-MH1-Pad16)") (class "Default")
      (node (ref "TR_DB15") (pin "16") (pinfunction "MH1_16") (pintype "passive"))
    )
    (net (code "164") (name "unconnected-(TR_DB15-MH2-Pad17)") (class "Default")
      (node (ref "TR_DB15") (pin "17") (pinfunction "MH2_17") (pintype "passive"))
    )
    (net (code "165") (name "unconnected-(TR_DB15-Pad1)") (class "Default")
      (node (ref "TR_DB15") (pin "1") (pinfunction "1_1") (pintype "passive"))
    )
    (net (code "166") (name "unconnected-(TR_DB15-Pad2)") (class "Default")
      (node (ref "TR_DB15") (pin "2") (pinfunction "2_2") (pintype "passive"))
    )
    (net (code "167") (name "unconnected-(TR_DB15-Pad5)") (class "Default")
      (node (ref "TR_DB15") (pin "5") (pinfunction "5_5") (pintype "passive"))
    )
    (net (code "168") (name "unconnected-(TR_DB15-Pad6)") (class "Default")
      (node (ref "TR_DB15") (pin "6") (pinfunction "6_6") (pintype "passive"))
    )
    (net (code "169") (name "unconnected-(TR_DB15-Pad7)") (class "Default")
      (node (ref "TR_DB15") (pin "7") (pinfunction "7_7") (pintype "passive"))
    )
    (net (code "170") (name "unconnected-(TR_DB15-Pad8)") (class "Default")
      (node (ref "TR_DB15") (pin "8") (pinfunction "8_8") (pintype "passive"))
    )
    (net (code "171") (name "unconnected-(TR_DB15-Pad9)") (class "Default")
      (node (ref "TR_DB15") (pin "9") (pinfunction "9_9") (pintype "passive"))
    )
    (net (code "172") (name "unconnected-(TR_DB15-Pad12)") (class "Default")
      (node (ref "TR_DB15") (pin "12") (pinfunction "12_12") (pintype "passive"))
    )
    (net (code "173") (name "unconnected-(TR_DB15-Pad13)") (class "Default")
      (node (ref "TR_DB15") (pin "13") (pinfunction "13_13") (pintype "passive"))
    )
    (net (code "174") (name "unconnected-(TR_DB15-Pad14)") (class "Default")
      (node (ref "TR_DB15") (pin "14") (pinfunction "14_14") (pintype "passive"))
    )
    (net (code "175") (name "unconnected-(TR_DB15-Pad15)") (class "Default")
      (node (ref "TR_DB15") (pin "15") (pinfunction "15_15") (pintype "passive"))
    )
    (net (code "176") (name "unconnected-(UMB_DB9_1-MH1-Pad10)") (class "Default")
      (node (ref "UMB_DB9_1") (pin "10") (pinfunction "MH1_10") (pintype "passive"))
    )
    (net (code "177") (name "unconnected-(UMB_DB9_1-MH2-Pad11)") (class "Default")
      (node (ref "UMB_DB9_1") (pin "11") (pinfunction "MH2_11") (pintype "passive"))
    )
    (net (code "178") (name "unconnected-(UMB_DB9_2-MH1-Pad10)") (class "Default")
      (node (ref "UMB_DB9_2") (pin "10") (pinfunction "MH1_10") (pintype "passive"))
    )
    (net (code "179") (name "unconnected-(UMB_DB9_2-MH2-Pad11)") (class "Default")
      (node (ref "UMB_DB9_2") (pin "11") (pinfunction "MH2_11") (pintype "passive"))
    )
  )
)
